# EN-C200_RA0_MCU.net
KiCad netlist of a schematic drawn in Altium Designer
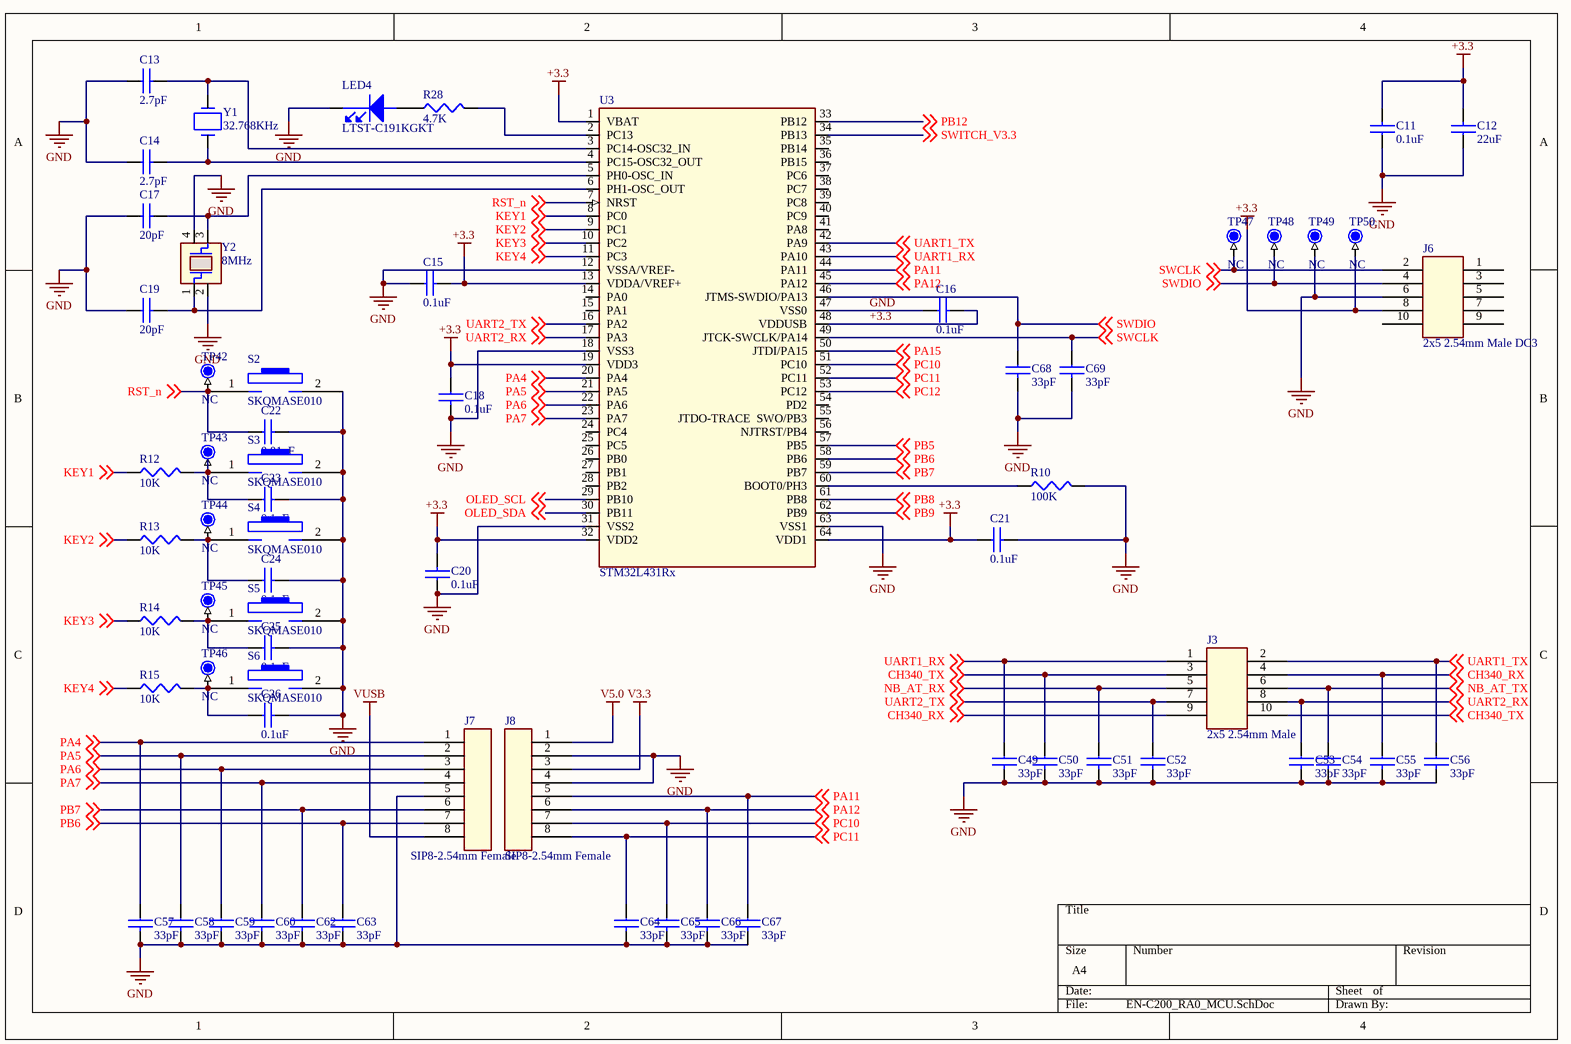
[diagram p0: EN-C200_RA0_MCU.SchDoc]

(export (version "E")
  (design (tool "Eeschema 10.0.6"))
  (components
    (comp (ref "C11") (value "0.1uF") (footprint "SC0603") (libsource (lib "EN-C200_RA0") (part "CAP NP")))
    (comp (ref "C12") (value "22uF") (footprint "SC0805") (libsource (lib "EN-C200_RA0") (part "CAP NP")))
    (comp (ref "C13") (value "2.7pF") (footprint "SC0603") (libsource (lib "EN-C200_RA0") (part "CAP NP")))
    (comp (ref "C14") (value "2.7pF") (footprint "SC0603") (libsource (lib "EN-C200_RA0") (part "CAP NP")))
    (comp (ref "C15") (value "0.1uF") (footprint "SC0603") (libsource (lib "EN-C200_RA0") (part "CAP NP")))
    (comp (ref "C16") (value "0.1uF") (footprint "SC0603") (libsource (lib "EN-C200_RA0") (part "CAP NP")))
    (comp (ref "C17") (value "20pF") (footprint "SC0603") (libsource (lib "EN-C200_RA0") (part "CAP NP")))
    (comp (ref "C18") (value "0.1uF") (footprint "SC0603") (libsource (lib "EN-C200_RA0") (part "CAP NP")))
    (comp (ref "C19") (value "20pF") (footprint "SC0603") (libsource (lib "EN-C200_RA0") (part "CAP NP")))
    (comp (ref "C20") (value "0.1uF") (footprint "SC0603") (libsource (lib "EN-C200_RA0") (part "CAP NP")))
    (comp (ref "C21") (value "0.1uF") (footprint "SC0603") (libsource (lib "EN-C200_RA0") (part "CAP NP")))
    (comp (ref "C22") (value "0.01uF") (footprint "SC0603") (libsource (lib "EN-C200_RA0") (part "CAP NP")))
    (comp (ref "C23") (value "0.1uF") (footprint "SC0603") (libsource (lib "EN-C200_RA0") (part "CAP NP")))
    (comp (ref "C24") (value "0.1uF") (footprint "SC0603") (libsource (lib "EN-C200_RA0") (part "CAP NP")))
    (comp (ref "C25") (value "0.1uF") (footprint "SC0603") (libsource (lib "EN-C200_RA0") (part "CAP NP")))
    (comp (ref "C26") (value "0.1uF") (footprint "SC0603") (libsource (lib "EN-C200_RA0") (part "CAP NP")))
    (comp (ref "C49") (value "33pF") (libsource (lib "EN-C200_RA0") (part "CAP NP")))
    (comp (ref "C50") (value "33pF") (libsource (lib "EN-C200_RA0") (part "CAP NP")))
    (comp (ref "C51") (value "33pF") (libsource (lib "EN-C200_RA0") (part "CAP NP")))
    (comp (ref "C52") (value "33pF") (libsource (lib "EN-C200_RA0") (part "CAP NP")))
    (comp (ref "C53") (value "33pF") (libsource (lib "EN-C200_RA0") (part "CAP NP")))
    (comp (ref "C54") (value "33pF") (libsource (lib "EN-C200_RA0") (part "CAP NP")))
    (comp (ref "C55") (value "33pF") (libsource (lib "EN-C200_RA0") (part "CAP NP")))
    (comp (ref "C56") (value "33pF") (libsource (lib "EN-C200_RA0") (part "CAP NP")))
    (comp (ref "C57") (value "33pF") (libsource (lib "EN-C200_RA0") (part "CAP NP")))
    (comp (ref "C58") (value "33pF") (libsource (lib "EN-C200_RA0") (part "CAP NP")))
    (comp (ref "C59") (value "33pF") (libsource (lib "EN-C200_RA0") (part "CAP NP")))
    (comp (ref "C60") (value "33pF") (libsource (lib "EN-C200_RA0") (part "CAP NP")))
    (comp (ref "C62") (value "33pF") (libsource (lib "EN-C200_RA0") (part "CAP NP")))
    (comp (ref "C63") (value "33pF") (libsource (lib "EN-C200_RA0") (part "CAP NP")))
    (comp (ref "C64") (value "33pF") (libsource (lib "EN-C200_RA0") (part "CAP NP")))
    (comp (ref "C65") (value "33pF") (libsource (lib "EN-C200_RA0") (part "CAP NP")))
    (comp (ref "C66") (value "33pF") (libsource (lib "EN-C200_RA0") (part "CAP NP")))
    (comp (ref "C67") (value "33pF") (libsource (lib "EN-C200_RA0") (part "CAP NP")))
    (comp (ref "C68") (value "33pF") (libsource (lib "EN-C200_RA0") (part "CAP NP")))
    (comp (ref "C69") (value "33pF") (libsource (lib "EN-C200_RA0") (part "CAP NP")))
    (comp (ref "J3")
      (value "2x5 2.54mm Male")
      (footprint "SIP-2X5P-100")
      (libsource (lib "") (part "CON10A_1"))
    )
    (comp (ref "J6")
      (value "2x5 2.54mm Male DC3")
      (footprint "SIP-2X5P-100-DS")
      (libsource (lib "EN-C200_RA0") (part "CON10A"))
    )
    (comp (ref "J7")
      (value "SIP8-2.54mm Female")
      (footprint "SIP-8P-100")
      (libsource (lib "") (part "HEADER8_1"))
    )
    (comp (ref "J8")
      (value "SIP8-2.54mm Female")
      (footprint "SIP-8P-100")
      (libsource (lib "EN-C200_RA0") (part "HEADER8"))
    )
    (comp (ref "LED4")
      (value "LTST-C191KGKT")
      (footprint "HSD0603-LED")
      (libsource (lib "EN-C200_RA0") (part "LED"))
    )
    (comp (ref "R10") (value "100K") (footprint "SR0603") (libsource (lib "EN-C200_RA0") (part "RESISTOR")))
    (comp (ref "R12") (value "10K") (footprint "SR0603") (libsource (lib "EN-C200_RA0") (part "RESISTOR")))
    (comp (ref "R13") (value "10K") (footprint "SR0603") (libsource (lib "EN-C200_RA0") (part "RESISTOR")))
    (comp (ref "R14") (value "10K") (footprint "SR0603") (libsource (lib "EN-C200_RA0") (part "RESISTOR")))
    (comp (ref "R15") (value "10K") (footprint "SR0603") (libsource (lib "EN-C200_RA0") (part "RESISTOR")))
    (comp (ref "R28") (value "4.7K") (footprint "SR0603") (libsource (lib "EN-C200_RA0") (part "RESISTOR")))
    (comp (ref "S2")
      (value "SKQMASE010")
      (footprint "SW2-240X140")
      (libsource (lib "EN-C200_RA0") (part "PUSH-KEY"))
    )
    (comp (ref "S3")
      (value "SKQMASE010")
      (footprint "SW2-240X140")
      (libsource (lib "EN-C200_RA0") (part "PUSH-KEY"))
    )
    (comp (ref "S4")
      (value "SKQMASE010")
      (footprint "SW2-240X140")
      (libsource (lib "EN-C200_RA0") (part "PUSH-KEY"))
    )
    (comp (ref "S5")
      (value "SKQMASE010")
      (footprint "SW2-240X140")
      (libsource (lib "EN-C200_RA0") (part "PUSH-KEY"))
    )
    (comp (ref "S6")
      (value "SKQMASE010")
      (footprint "SW2-240X140")
      (libsource (lib "EN-C200_RA0") (part "PUSH-KEY"))
    )
    (comp (ref "TP42") (value "NC") (footprint "TP32-SMD") (libsource (lib "EN-C200_RA0") (part "TP")))
    (comp (ref "TP43") (value "NC") (footprint "TP32-SMD") (libsource (lib "EN-C200_RA0") (part "TP")))
    (comp (ref "TP44") (value "NC") (footprint "TP32-SMD") (libsource (lib "EN-C200_RA0") (part "TP")))
    (comp (ref "TP45") (value "NC") (footprint "TP32-SMD") (libsource (lib "EN-C200_RA0") (part "TP")))
    (comp (ref "TP46") (value "NC") (footprint "TP32-SMD") (libsource (lib "EN-C200_RA0") (part "TP")))
    (comp (ref "TP47") (value "NC") (libsource (lib "EN-C200_RA0") (part "TP")))
    (comp (ref "TP48") (value "NC") (libsource (lib "EN-C200_RA0") (part "TP")))
    (comp (ref "TP49") (value "NC") (libsource (lib "EN-C200_RA0") (part "TP")))
    (comp (ref "TP50") (value "NC") (libsource (lib "EN-C200_RA0") (part "TP")))
    (comp (ref "U3")
      (value "STM32L431Rx")
      (footprint "QFP64D-050-1010L")
      (libsource (lib "EN-C200_RA0") (part "STM32L431Rx"))
    )
    (comp (ref "Y1")
      (value "32.768KHz")
      (footprint "FC-135_110")
      (libsource (lib "EN-C200_RA0") (part "CRYSTAL2P"))
    )
    (comp (ref "Y2")
      (value "8MHz")
      (footprint "HSX4-0503B")
      (libsource (lib "EN-C200_RA0") (part "CRYSTAL4P"))
    )
  )
  (nets
    (net (code "1") (name "+3.3") (class "Default")
      (node (ref "C11") (pin "2") (pinfunction "2_2") (pintype "passive"))
      (node (ref "C12") (pin "2") (pinfunction "2_2") (pintype "passive"))
      (node (ref "C15") (pin "2") (pinfunction "2_2") (pintype "passive"))
      (node (ref "C16") (pin "2") (pinfunction "2_2") (pintype "passive"))
      (node (ref "C18") (pin "1") (pinfunction "1_1") (pintype "passive"))
      (node (ref "C20") (pin "2") (pinfunction "2_2") (pintype "passive"))
      (node (ref "C21") (pin "1") (pinfunction "1_1") (pintype "passive"))
      (node (ref "J6") (pin "8") (pinfunction "8_8") (pintype "passive"))
      (node (ref "TP50") (pin "1") (pinfunction "1_1") (pintype "input"))
      (node (ref "U3") (pin "1") (pinfunction "VBAT_1") (pintype "power_in"))
      (node (ref "U3") (pin "13") (pinfunction "VDDA/VREF+_13") (pintype "power_in"))
      (node (ref "U3") (pin "19") (pinfunction "VDD3_19") (pintype "power_in"))
      (node (ref "U3") (pin "32") (pinfunction "VDD2_32") (pintype "power_in"))
      (node (ref "U3") (pin "48") (pinfunction "VDDUSB_48") (pintype "power_in"))
      (node (ref "U3") (pin "64") (pinfunction "VDD1_64") (pintype "power_in"))
    )
    (net (code "2") (name "CH340_RX") (class "Default")
      (node (ref "C55") (pin "1") (pinfunction "1_1") (pintype "passive"))
      (node (ref "J3") (pin "4") (pinfunction "4_4") (pintype "passive"))
      (node (ref "J3") (pin "9") (pinfunction "9_9") (pintype "passive"))
    )
    (net (code "3") (name "CH340_TX") (class "Default")
      (node (ref "C50") (pin "1") (pinfunction "1_1") (pintype "passive"))
      (node (ref "J3") (pin "10") (pinfunction "10_10") (pintype "passive"))
      (node (ref "J3") (pin "3") (pinfunction "3_3") (pintype "passive"))
    )
    (net (code "4") (name "GND") (class "Default")
      (node (ref "C11") (pin "1") (pinfunction "1_1") (pintype "passive"))
      (node (ref "C12") (pin "1") (pinfunction "1_1") (pintype "passive"))
      (node (ref "C13") (pin "1") (pinfunction "1_1") (pintype "passive"))
      (node (ref "C14") (pin "1") (pinfunction "1_1") (pintype "passive"))
      (node (ref "C15") (pin "1") (pinfunction "1_1") (pintype "passive"))
      (node (ref "C16") (pin "1") (pinfunction "1_1") (pintype "passive"))
      (node (ref "C17") (pin "1") (pinfunction "1_1") (pintype "passive"))
      (node (ref "C18") (pin "2") (pinfunction "2_2") (pintype "passive"))
      (node (ref "C19") (pin "1") (pinfunction "1_1") (pintype "passive"))
      (node (ref "C20") (pin "1") (pinfunction "1_1") (pintype "passive"))
      (node (ref "C21") (pin "2") (pinfunction "2_2") (pintype "passive"))
      (node (ref "C22") (pin "2") (pinfunction "2_2") (pintype "passive"))
      (node (ref "C23") (pin "2") (pinfunction "2_2") (pintype "passive"))
      (node (ref "C24") (pin "2") (pinfunction "2_2") (pintype "passive"))
      (node (ref "C25") (pin "2") (pinfunction "2_2") (pintype "passive"))
      (node (ref "C26") (pin "2") (pinfunction "2_2") (pintype "passive"))
      (node (ref "C49") (pin "2") (pinfunction "2_2") (pintype "passive"))
      (node (ref "C50") (pin "2") (pinfunction "2_2") (pintype "passive"))
      (node (ref "C51") (pin "2") (pinfunction "2_2") (pintype "passive"))
      (node (ref "C52") (pin "2") (pinfunction "2_2") (pintype "passive"))
      (node (ref "C53") (pin "2") (pinfunction "2_2") (pintype "passive"))
      (node (ref "C54") (pin "2") (pinfunction "2_2") (pintype "passive"))
      (node (ref "C55") (pin "2") (pinfunction "2_2") (pintype "passive"))
      (node (ref "C56") (pin "2") (pinfunction "2_2") (pintype "passive"))
      (node (ref "C57") (pin "2") (pinfunction "2_2") (pintype "passive"))
      (node (ref "C58") (pin "2") (pinfunction "2_2") (pintype "passive"))
      (node (ref "C59") (pin "2") (pinfunction "2_2") (pintype "passive"))
      (node (ref "C60") (pin "2") (pinfunction "2_2") (pintype "passive"))
      (node (ref "C62") (pin "2") (pinfunction "2_2") (pintype "passive"))
      (node (ref "C63") (pin "2") (pinfunction "2_2") (pintype "passive"))
      (node (ref "C64") (pin "2") (pinfunction "2_2") (pintype "passive"))
      (node (ref "C65") (pin "2") (pinfunction "2_2") (pintype "passive"))
      (node (ref "C66") (pin "2") (pinfunction "2_2") (pintype "passive"))
      (node (ref "C67") (pin "2") (pinfunction "2_2") (pintype "passive"))
      (node (ref "C68") (pin "2") (pinfunction "2_2") (pintype "passive"))
      (node (ref "C69") (pin "2") (pinfunction "2_2") (pintype "passive"))
      (node (ref "J6") (pin "6") (pinfunction "6_6") (pintype "passive"))
      (node (ref "J7") (pin "5") (pinfunction "5_5") (pintype "passive"))
      (node (ref "J8") (pin "2") (pinfunction "2_2") (pintype "passive"))
      (node (ref "J8") (pin "4") (pinfunction "4_4") (pintype "passive"))
      (node (ref "LED4") (pin "2") (pinfunction "2_2") (pintype "passive"))
      (node (ref "R10") (pin "2") (pinfunction "2_2") (pintype "passive"))
      (node (ref "S2") (pin "2") (pinfunction "B_2") (pintype "passive"))
      (node (ref "S3") (pin "2") (pinfunction "B_2") (pintype "passive"))
      (node (ref "S4") (pin "2") (pinfunction "B_2") (pintype "passive"))
      (node (ref "S5") (pin "2") (pinfunction "B_2") (pintype "passive"))
      (node (ref "S6") (pin "2") (pinfunction "B_2") (pintype "passive"))
      (node (ref "TP49") (pin "1") (pinfunction "1_1") (pintype "input"))
      (node (ref "U3") (pin "12") (pinfunction "VSSA/VREF-_12") (pintype "power_in"))
      (node (ref "U3") (pin "18") (pinfunction "VSS3_18") (pintype "power_in"))
      (node (ref "U3") (pin "31") (pinfunction "VSS2_31") (pintype "power_in"))
      (node (ref "U3") (pin "47") (pinfunction "VSS0_47") (pintype "power_in"))
      (node (ref "U3") (pin "63") (pinfunction "VSS1_63") (pintype "power_in"))
      (node (ref "Y2") (pin "2") (pinfunction "2_2") (pintype "passive"))
      (node (ref "Y2") (pin "4") (pinfunction "4_4") (pintype "passive"))
    )
    (net (code "5") (name "KEY1") (class "Default")
      (node (ref "R12") (pin "1") (pinfunction "1_1") (pintype "passive"))
      (node (ref "U3") (pin "8") (pinfunction "PC0_8") (pintype "bidirectional"))
    )
    (net (code "6") (name "KEY2") (class "Default")
      (node (ref "R13") (pin "1") (pinfunction "1_1") (pintype "passive"))
      (node (ref "U3") (pin "9") (pinfunction "PC1_9") (pintype "bidirectional"))
    )
    (net (code "7") (name "KEY3") (class "Default")
      (node (ref "R14") (pin "1") (pinfunction "1_1") (pintype "passive"))
      (node (ref "U3") (pin "10") (pinfunction "PC2_10") (pintype "bidirectional"))
    )
    (net (code "8") (name "KEY4") (class "Default")
      (node (ref "R15") (pin "1") (pinfunction "1_1") (pintype "passive"))
      (node (ref "U3") (pin "11") (pinfunction "PC3_11") (pintype "bidirectional"))
    )
    (net (code "9") (name "NB_AT_RX") (class "Default")
      (node (ref "C51") (pin "1") (pinfunction "1_1") (pintype "passive"))
      (node (ref "J3") (pin "5") (pinfunction "5_5") (pintype "passive"))
    )
    (net (code "10") (name "NB_AT_TX") (class "Default")
      (node (ref "C54") (pin "1") (pinfunction "1_1") (pintype "passive"))
      (node (ref "J3") (pin "6") (pinfunction "6_6") (pintype "passive"))
    )
    (net (code "11") (name "Net-(LED4-Pad1)") (class "Default")
      (node (ref "LED4") (pin "1") (pinfunction "1_1") (pintype "passive"))
      (node (ref "R28") (pin "1") (pinfunction "1_1") (pintype "passive"))
    )
    (net (code "12") (name "Net-(S3-A)") (class "Default")
      (node (ref "C23") (pin "1") (pinfunction "1_1") (pintype "passive"))
      (node (ref "R12") (pin "2") (pinfunction "2_2") (pintype "passive"))
      (node (ref "S3") (pin "1") (pinfunction "A_1") (pintype "passive"))
      (node (ref "TP43") (pin "1") (pinfunction "1_1") (pintype "input"))
    )
    (net (code "13") (name "Net-(S4-A)") (class "Default")
      (node (ref "C24") (pin "1") (pinfunction "1_1") (pintype "passive"))
      (node (ref "R13") (pin "2") (pinfunction "2_2") (pintype "passive"))
      (node (ref "S4") (pin "1") (pinfunction "A_1") (pintype "passive"))
      (node (ref "TP44") (pin "1") (pinfunction "1_1") (pintype "input"))
    )
    (net (code "14") (name "Net-(S5-A)") (class "Default")
      (node (ref "C25") (pin "1") (pinfunction "1_1") (pintype "passive"))
      (node (ref "R14") (pin "2") (pinfunction "2_2") (pintype "passive"))
      (node (ref "S5") (pin "1") (pinfunction "A_1") (pintype "passive"))
      (node (ref "TP45") (pin "1") (pinfunction "1_1") (pintype "input"))
    )
    (net (code "15") (name "Net-(S6-A)") (class "Default")
      (node (ref "C26") (pin "1") (pinfunction "1_1") (pintype "passive"))
      (node (ref "R15") (pin "2") (pinfunction "2_2") (pintype "passive"))
      (node (ref "S6") (pin "1") (pinfunction "A_1") (pintype "passive"))
      (node (ref "TP46") (pin "1") (pinfunction "1_1") (pintype "input"))
    )
    (net (code "16") (name "Net-(U3-BOOT0{slash}PH3)") (class "Default")
      (node (ref "R10") (pin "1") (pinfunction "1_1") (pintype "passive"))
      (node (ref "U3") (pin "60") (pinfunction "BOOT0/PH3_60") (pintype "bidirectional"))
    )
    (net (code "17") (name "Net-(U3-PC13)") (class "Default")
      (node (ref "R28") (pin "2") (pinfunction "2_2") (pintype "passive"))
      (node (ref "U3") (pin "2") (pinfunction "PC13_2") (pintype "bidirectional"))
    )
    (net (code "18") (name "Net-(U3-PC14-OSC32_IN)") (class "Default")
      (node (ref "C13") (pin "2") (pinfunction "2_2") (pintype "passive"))
      (node (ref "U3") (pin "3") (pinfunction "PC14-OSC32_IN_3") (pintype "bidirectional"))
      (node (ref "Y1") (pin "2") (pinfunction "2_2") (pintype "passive"))
    )
    (net (code "19") (name "Net-(U3-PC15-OSC32_OUT)") (class "Default")
      (node (ref "C14") (pin "2") (pinfunction "2_2") (pintype "passive"))
      (node (ref "U3") (pin "4") (pinfunction "PC15-OSC32_OUT_4") (pintype "bidirectional"))
      (node (ref "Y1") (pin "1") (pinfunction "1_1") (pintype "passive"))
    )
    (net (code "20") (name "Net-(U3-PH0-OSC_IN)") (class "Default")
      (node (ref "C17") (pin "2") (pinfunction "2_2") (pintype "passive"))
      (node (ref "U3") (pin "5") (pinfunction "PH0-OSC_IN_5") (pintype "bidirectional"))
      (node (ref "Y2") (pin "3") (pinfunction "COUT_3") (pintype "passive"))
    )
    (net (code "21") (name "Net-(U3-PH1-OSC_OUT)") (class "Default")
      (node (ref "C19") (pin "2") (pinfunction "2_2") (pintype "passive"))
      (node (ref "U3") (pin "6") (pinfunction "PH1-OSC_OUT_6") (pintype "bidirectional"))
      (node (ref "Y2") (pin "1") (pinfunction "CIN_1") (pintype "passive"))
    )
    (net (code "22") (name "OLED_SCL") (class "Default")
      (node (ref "U3") (pin "29") (pinfunction "PB10_29") (pintype "bidirectional"))
    )
    (net (code "23") (name "OLED_SDA") (class "Default")
      (node (ref "U3") (pin "30") (pinfunction "PB11_30") (pintype "bidirectional"))
    )
    (net (code "24") (name "PA4") (class "Default")
      (node (ref "C57") (pin "1") (pinfunction "1_1") (pintype "passive"))
      (node (ref "J7") (pin "1") (pinfunction "1_1") (pintype "passive"))
      (node (ref "U3") (pin "20") (pinfunction "PA4_20") (pintype "bidirectional"))
    )
    (net (code "25") (name "PA5") (class "Default")
      (node (ref "C58") (pin "1") (pinfunction "1_1") (pintype "passive"))
      (node (ref "J7") (pin "2") (pinfunction "2_2") (pintype "passive"))
      (node (ref "U3") (pin "21") (pinfunction "PA5_21") (pintype "bidirectional"))
    )
    (net (code "26") (name "PA6") (class "Default")
      (node (ref "C59") (pin "1") (pinfunction "1_1") (pintype "passive"))
      (node (ref "J7") (pin "3") (pinfunction "3_3") (pintype "passive"))
      (node (ref "U3") (pin "22") (pinfunction "PA6_22") (pintype "bidirectional"))
    )
    (net (code "27") (name "PA7") (class "Default")
      (node (ref "C60") (pin "1") (pinfunction "1_1") (pintype "passive"))
      (node (ref "J7") (pin "4") (pinfunction "4_4") (pintype "passive"))
      (node (ref "U3") (pin "23") (pinfunction "PA7_23") (pintype "bidirectional"))
    )
    (net (code "28") (name "PA11") (class "Default")
      (node (ref "C67") (pin "1") (pinfunction "1_1") (pintype "passive"))
      (node (ref "J8") (pin "5") (pinfunction "5_5") (pintype "passive"))
      (node (ref "U3") (pin "44") (pinfunction "PA11_44") (pintype "bidirectional"))
    )
    (net (code "29") (name "PA12") (class "Default")
      (node (ref "C66") (pin "1") (pinfunction "1_1") (pintype "passive"))
      (node (ref "J8") (pin "6") (pinfunction "6_6") (pintype "passive"))
      (node (ref "U3") (pin "45") (pinfunction "PA12_45") (pintype "bidirectional"))
    )
    (net (code "30") (name "PA15") (class "Default")
      (node (ref "U3") (pin "50") (pinfunction "JTDI/PA15_50") (pintype "bidirectional"))
    )
    (net (code "31") (name "PB5") (class "Default")
      (node (ref "U3") (pin "57") (pinfunction "PB5_57") (pintype "bidirectional"))
    )
    (net (code "32") (name "PB6") (class "Default")
      (node (ref "C63") (pin "1") (pinfunction "1_1") (pintype "passive"))
      (node (ref "J7") (pin "7") (pinfunction "7_7") (pintype "passive"))
      (node (ref "U3") (pin "58") (pinfunction "PB6_58") (pintype "bidirectional"))
    )
    (net (code "33") (name "PB7") (class "Default")
      (node (ref "C62") (pin "1") (pinfunction "1_1") (pintype "passive"))
      (node (ref "J7") (pin "6") (pinfunction "6_6") (pintype "passive"))
      (node (ref "U3") (pin "59") (pinfunction "PB7_59") (pintype "bidirectional"))
    )
    (net (code "34") (name "PB8") (class "Default")
      (node (ref "U3") (pin "61") (pinfunction "PB8_61") (pintype "bidirectional"))
    )
    (net (code "35") (name "PB9") (class "Default")
      (node (ref "U3") (pin "62") (pinfunction "PB9_62") (pintype "bidirectional"))
    )
    (net (code "36") (name "PB12") (class "Default")
      (node (ref "U3") (pin "33") (pinfunction "PB12_33") (pintype "bidirectional"))
    )
    (net (code "37") (name "PC10") (class "Default")
      (node (ref "C65") (pin "1") (pinfunction "1_1") (pintype "passive"))
      (node (ref "J8") (pin "7") (pinfunction "7_7") (pintype "passive"))
      (node (ref "U3") (pin "51") (pinfunction "PC10_51") (pintype "bidirectional"))
    )
    (net (code "38") (name "PC11") (class "Default")
      (node (ref "C64") (pin "1") (pinfunction "1_1") (pintype "passive"))
      (node (ref "J8") (pin "8") (pinfunction "8_8") (pintype "passive"))
      (node (ref "U3") (pin "52") (pinfunction "PC11_52") (pintype "bidirectional"))
    )
    (net (code "39") (name "PC12") (class "Default")
      (node (ref "U3") (pin "53") (pinfunction "PC12_53") (pintype "bidirectional"))
    )
    (net (code "40") (name "RST_n") (class "Default")
      (node (ref "C22") (pin "1") (pinfunction "1_1") (pintype "passive"))
      (node (ref "S2") (pin "1") (pinfunction "A_1") (pintype "passive"))
      (node (ref "TP42") (pin "1") (pinfunction "1_1") (pintype "input"))
      (node (ref "U3") (pin "7") (pinfunction "NRST_7") (pintype "input"))
    )
    (net (code "41") (name "SWCLK") (class "Default")
      (node (ref "C69") (pin "1") (pinfunction "1_1") (pintype "passive"))
      (node (ref "J6") (pin "2") (pinfunction "2_2") (pintype "passive"))
      (node (ref "TP47") (pin "1") (pinfunction "1_1") (pintype "input"))
      (node (ref "U3") (pin "49") (pinfunction "JTCK-SWCLK/PA14_49") (pintype "bidirectional"))
    )
    (net (code "42") (name "SWDIO") (class "Default")
      (node (ref "C68") (pin "1") (pinfunction "1_1") (pintype "passive"))
      (node (ref "J6") (pin "4") (pinfunction "4_4") (pintype "passive"))
      (node (ref "TP48") (pin "1") (pinfunction "1_1") (pintype "input"))
      (node (ref "U3") (pin "46") (pinfunction "JTMS-SWDIO/PA13_46") (pintype "bidirectional"))
    )
    (net (code "43") (name "SWITCH_V3.3") (class "Default")
      (node (ref "U3") (pin "34") (pinfunction "PB13_34") (pintype "bidirectional"))
    )
    (net (code "44") (name "UART1_RX") (class "Default")
      (node (ref "C49") (pin "1") (pinfunction "1_1") (pintype "passive"))
      (node (ref "J3") (pin "1") (pinfunction "1_1") (pintype "passive"))
      (node (ref "U3") (pin "43") (pinfunction "PA10_43") (pintype "bidirectional"))
    )
    (net (code "45") (name "UART1_TX") (class "Default")
      (node (ref "C56") (pin "1") (pinfunction "1_1") (pintype "passive"))
      (node (ref "J3") (pin "2") (pinfunction "2_2") (pintype "passive"))
      (node (ref "U3") (pin "42") (pinfunction "PA9_42") (pintype "bidirectional"))
    )
    (net (code "46") (name "UART2_RX") (class "Default")
      (node (ref "C53") (pin "1") (pinfunction "1_1") (pintype "passive"))
      (node (ref "J3") (pin "8") (pinfunction "8_8") (pintype "passive"))
      (node (ref "U3") (pin "17") (pinfunction "PA3_17") (pintype "bidirectional"))
    )
    (net (code "47") (name "UART2_TX") (class "Default")
      (node (ref "C52") (pin "1") (pinfunction "1_1") (pintype "passive"))
      (node (ref "J3") (pin "7") (pinfunction "7_7") (pintype "passive"))
      (node (ref "U3") (pin "16") (pinfunction "PA2_16") (pintype "bidirectional"))
    )
    (net (code "48") (name "V3.3") (class "Default")
      (node (ref "J8") (pin "3") (pinfunction "3_3") (pintype "passive"))
    )
    (net (code "49") (name "V5.0") (class "Default")
      (node (ref "J8") (pin "1") (pinfunction "1_1") (pintype "passive"))
    )
    (net (code "50") (name "VUSB") (class "Default")
      (node (ref "J7") (pin "8") (pinfunction "8_8") (pintype "passive"))
    )
    (net (code "51") (name "unconnected-(J6-Pad1)") (class "Default")
      (node (ref "J6") (pin "1") (pinfunction "1_1") (pintype "passive"))
    )
    (net (code "52") (name "unconnected-(J6-Pad3)") (class "Default")
      (node (ref "J6") (pin "3") (pinfunction "3_3") (pintype "passive"))
    )
    (net (code "53") (name "unconnected-(J6-Pad5)") (class "Default")
      (node (ref "J6") (pin "5") (pinfunction "5_5") (pintype "passive"))
    )
    (net (code "54") (name "unconnected-(J6-Pad7)") (class "Default")
      (node (ref "J6") (pin "7") (pinfunction "7_7") (pintype "passive"))
    )
    (net (code "55") (name "unconnected-(J6-Pad9)") (class "Default")
      (node (ref "J6") (pin "9") (pinfunction "9_9") (pintype "passive"))
    )
    (net (code "56") (name "unconnected-(J6-Pad10)") (class "Default")
      (node (ref "J6") (pin "10") (pinfunction "10_10") (pintype "passive"))
    )
    (net (code "57") (name "unconnected-(U3-JTDO-TRACE__SWO{slash}PB3-Pad55)") (class "Default")
      (node (ref "U3") (pin "55") (pinfunction "JTDO-TRACE__SWO/PB3_55") (pintype "bidirectional"))
    )
    (net (code "58") (name "unconnected-(U3-NJTRST{slash}PB4-Pad56)") (class "Default")
      (node (ref "U3") (pin "56") (pinfunction "NJTRST/PB4_56") (pintype "bidirectional"))
    )
    (net (code "59") (name "unconnected-(U3-PA0-Pad14)") (class "Default")
      (node (ref "U3") (pin "14") (pinfunction "PA0_14") (pintype "bidirectional"))
    )
    (net (code "60") (name "unconnected-(U3-PA1-Pad15)") (class "Default")
      (node (ref "U3") (pin "15") (pinfunction "PA1_15") (pintype "bidirectional"))
    )
    (net (code "61") (name "unconnected-(U3-PA8-Pad41)") (class "Default")
      (node (ref "U3") (pin "41") (pinfunction "PA8_41") (pintype "bidirectional"))
    )
    (net (code "62") (name "unconnected-(U3-PB0-Pad26)") (class "Default")
      (node (ref "U3") (pin "26") (pinfunction "PB0_26") (pintype "bidirectional"))
    )
    (net (code "63") (name "unconnected-(U3-PB1-Pad27)") (class "Default")
      (node (ref "U3") (pin "27") (pinfunction "PB1_27") (pintype "bidirectional"))
    )
    (net (code "64") (name "unconnected-(U3-PB2-Pad28)") (class "Default")
      (node (ref "U3") (pin "28") (pinfunction "PB2_28") (pintype "bidirectional"))
    )
    (net (code "65") (name "unconnected-(U3-PB14-Pad35)") (class "Default")
      (node (ref "U3") (pin "35") (pinfunction "PB14_35") (pintype "bidirectional"))
    )
    (net (code "66") (name "unconnected-(U3-PB15-Pad36)") (class "Default")
      (node (ref "U3") (pin "36") (pinfunction "PB15_36") (pintype "bidirectional"))
    )
    (net (code "67") (name "unconnected-(U3-PC4-Pad24)") (class "Default")
      (node (ref "U3") (pin "24") (pinfunction "PC4_24") (pintype "bidirectional"))
    )
    (net (code "68") (name "unconnected-(U3-PC5-Pad25)") (class "Default")
      (node (ref "U3") (pin "25") (pinfunction "PC5_25") (pintype "bidirectional"))
    )
    (net (code "69") (name "unconnected-(U3-PC6-Pad37)") (class "Default")
      (node (ref "U3") (pin "37") (pinfunction "PC6_37") (pintype "bidirectional"))
    )
    (net (code "70") (name "unconnected-(U3-PC7-Pad38)") (class "Default")
      (node (ref "U3") (pin "38") (pinfunction "PC7_38") (pintype "bidirectional"))
    )
    (net (code "71") (name "unconnected-(U3-PC8-Pad39)") (class "Default")
      (node (ref "U3") (pin "39") (pinfunction "PC8_39") (pintype "bidirectional"))
    )
    (net (code "72") (name "unconnected-(U3-PC9-Pad40)") (class "Default")
      (node (ref "U3") (pin "40") (pinfunction "PC9_40") (pintype "bidirectional"))
    )
    (net (code "73") (name "unconnected-(U3-PD2-Pad54)") (class "Default")
      (node (ref "U3") (pin "54") (pinfunction "PD2_54") (pintype "bidirectional"))
    )
  )
)
